# LCD.net
KiCad netlist of a schematic drawn in Altium Designer
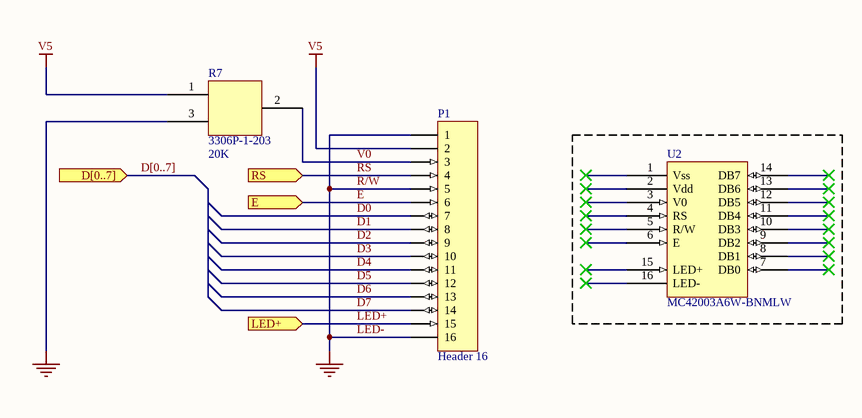
[diagram p0: LCD.SchDoc]

(export (version "E")
  (design (tool "Eeschema 10.0.6"))
  (components
    (comp (ref "P1")
      (value "Header 16")
      (footprint "Header 16")
      (description "Header, 16-Pin")
      (libsource (lib "Miscellaneous Connectors") (part "Header 16"))
    )
    (comp (ref "R7")
      (value "3306P-1-203")
      (footprint "3306P-1-202")
      (description "Trimpot")
      (fields (field (name "ALTIUM_VALUE") "20K"))
      (libsource (lib "Components") (part "3306P-1-202"))
    )
    (comp (ref "U2")
      (value "MC42003A6W-BNMLW")
      (footprint "MC42004A6W-BNMLW")
      (description "LCD")
      (libsource (lib "Components") (part "MC42003A6W-BNMLW"))
    )
  )
  (nets
    (net (code "1") (name "/D0") (class "Default")
      (node (ref "P1") (pin "7") (pinfunction "7_7") (pintype "bidirectional"))
    )
    (net (code "2") (name "/D1") (class "Default")
      (node (ref "P1") (pin "8") (pinfunction "8_8") (pintype "bidirectional"))
    )
    (net (code "3") (name "/D2") (class "Default")
      (node (ref "P1") (pin "9") (pinfunction "9_9") (pintype "bidirectional"))
    )
    (net (code "4") (name "/D3") (class "Default")
      (node (ref "P1") (pin "10") (pinfunction "10_10") (pintype "bidirectional"))
    )
    (net (code "5") (name "/D4") (class "Default")
      (node (ref "P1") (pin "11") (pinfunction "11_11") (pintype "bidirectional"))
    )
    (net (code "6") (name "/D5") (class "Default")
      (node (ref "P1") (pin "12") (pinfunction "12_12") (pintype "bidirectional"))
    )
    (net (code "7") (name "/D6") (class "Default")
      (node (ref "P1") (pin "13") (pinfunction "13_13") (pintype "bidirectional"))
    )
    (net (code "8") (name "/D7") (class "Default")
      (node (ref "P1") (pin "14") (pinfunction "14_14") (pintype "bidirectional"))
    )
    (net (code "10") (name "/E") (class "Default")
      (node (ref "P1") (pin "6") (pinfunction "6_6") (pintype "input"))
    )
    (net (code "11") (name "/LED+") (class "Default")
      (node (ref "P1") (pin "15") (pinfunction "15_15") (pintype "input"))
    )
    (net (code "12") (name "/RS") (class "Default")
      (node (ref "P1") (pin "4") (pinfunction "4_4") (pintype "input"))
    )
    (net (code "13") (name "/V0") (class "Default")
      (node (ref "P1") (pin "3") (pinfunction "3_3") (pintype "input"))
      (node (ref "R7") (pin "2") (pinfunction "2_2") (pintype "power_in"))
    )
    (net (code "14") (name "GND") (class "Default")
      (node (ref "P1") (pin "1") (pinfunction "1_1") (pintype "passive"))
      (node (ref "P1") (pin "16") (pinfunction "16_16") (pintype "passive"))
      (node (ref "P1") (pin "5") (pinfunction "5_5") (pintype "input"))
      (node (ref "R7") (pin "3") (pinfunction "3_3") (pintype "power_in"))
    )
    (net (code "15") (name "V5") (class "Default")
      (node (ref "P1") (pin "2") (pinfunction "2_2") (pintype "passive"))
      (node (ref "R7") (pin "1") (pinfunction "1_1") (pintype "power_in"))
    )
    (net (code "16") (name "unconnected-(U2-DB0-Pad7)") (class "Default")
      (node (ref "U2") (pin "7") (pinfunction "DB0_7") (pintype "bidirectional+no_connect"))
    )
    (net (code "17") (name "unconnected-(U2-DB1-Pad8)") (class "Default")
      (node (ref "U2") (pin "8") (pinfunction "DB1_8") (pintype "bidirectional+no_connect"))
    )
    (net (code "18") (name "unconnected-(U2-DB2-Pad9)") (class "Default")
      (node (ref "U2") (pin "9") (pinfunction "DB2_9") (pintype "bidirectional+no_connect"))
    )
    (net (code "19") (name "unconnected-(U2-DB3-Pad10)") (class "Default")
      (node (ref "U2") (pin "10") (pinfunction "DB3_10") (pintype "bidirectional+no_connect"))
    )
    (net (code "20") (name "unconnected-(U2-DB4-Pad11)") (class "Default")
      (node (ref "U2") (pin "11") (pinfunction "DB4_11") (pintype "bidirectional+no_connect"))
    )
    (net (code "21") (name "unconnected-(U2-DB5-Pad12)") (class "Default")
      (node (ref "U2") (pin "12") (pinfunction "DB5_12") (pintype "bidirectional+no_connect"))
    )
    (net (code "22") (name "unconnected-(U2-DB6-Pad13)") (class "Default")
      (node (ref "U2") (pin "13") (pinfunction "DB6_13") (pintype "bidirectional+no_connect"))
    )
    (net (code "23") (name "unconnected-(U2-DB7-Pad14)") (class "Default")
      (node (ref "U2") (pin "14") (pinfunction "DB7_14") (pintype "bidirectional+no_connect"))
    )
    (net (code "24") (name "unconnected-(U2-E-Pad6)") (class "Default")
      (node (ref "U2") (pin "6") (pinfunction "E_6") (pintype "input+no_connect"))
    )
    (net (code "25") (name "unconnected-(U2-LED+-Pad15)") (class "Default")
      (node (ref "U2") (pin "15") (pinfunction "LED+_15") (pintype "input+no_connect"))
    )
    (net (code "26") (name "unconnected-(U2-LED--Pad16)") (class "Default")
      (node (ref "U2") (pin "16") (pinfunction "LED-_16") (pintype "power_in+no_connect"))
    )
    (net (code "27") (name "unconnected-(U2-RS-Pad4)") (class "Default")
      (node (ref "U2") (pin "4") (pinfunction "RS_4") (pintype "input+no_connect"))
    )
    (net (code "28") (name "unconnected-(U2-R{slash}W-Pad5)") (class "Default")
      (node (ref "U2") (pin "5") (pinfunction "R/W_5") (pintype "input+no_connect"))
    )
    (net (code "29") (name "unconnected-(U2-V0-Pad3)") (class "Default")
      (node (ref "U2") (pin "3") (pinfunction "V0_3") (pintype "input+no_connect"))
    )
    (net (code "30") (name "unconnected-(U2-Vdd-Pad2)") (class "Default")
      (node (ref "U2") (pin "2") (pinfunction "Vdd_2") (pintype "power_in+no_connect"))
    )
    (net (code "31") (name "unconnected-(U2-Vss-Pad1)") (class "Default")
      (node (ref "U2") (pin "1") (pinfunction "Vss_1") (pintype "power_in+no_connect"))
    )
  )
)
